# JLink-OB.net
KiCad netlist of a schematic drawn in EAGLE
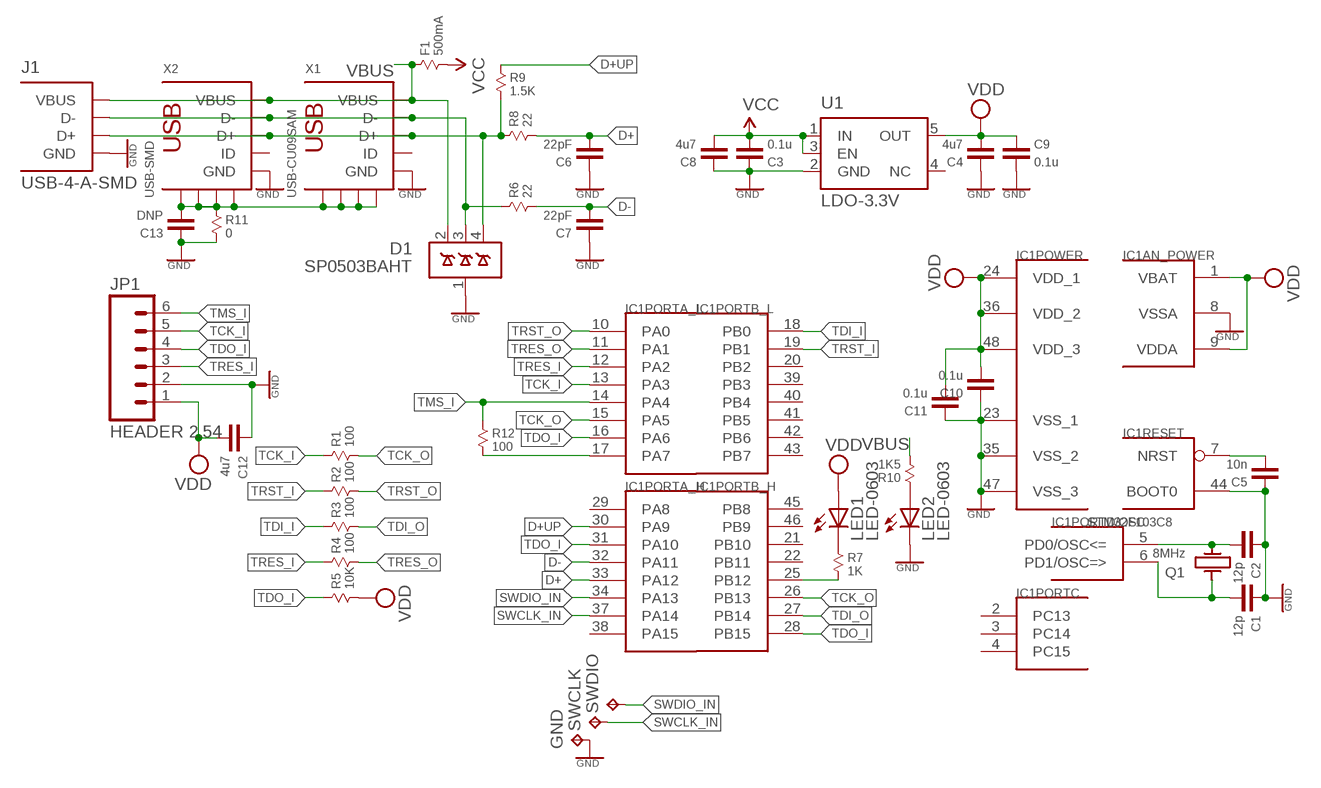
[diagram p0: schematic, sheet 1]

(export (version "E")
  (design (tool "Eeschema 10.0.6"))
  (components
    (comp (ref "C1")
      (value "12p")
      (footprint "eagle-import:0603")
      (libsource (lib "eagle-import") (part "CAP-0603"))
    )
    (comp (ref "C2")
      (value "12p")
      (footprint "eagle-import:0603")
      (libsource (lib "eagle-import") (part "CAP-0603"))
    )
    (comp (ref "C3")
      (value "0.1u")
      (footprint "eagle-import:0603")
      (libsource (lib "eagle-import") (part "CAP-0603"))
    )
    (comp (ref "C4")
      (value "4u7")
      (footprint "eagle-import:0603")
      (libsource (lib "eagle-import") (part "CAP-0603"))
    )
    (comp (ref "C5")
      (value "10n")
      (footprint "eagle-import:0603")
      (libsource (lib "eagle-import") (part "CAP-0603"))
    )
    (comp (ref "C6")
      (value "22pF")
      (footprint "eagle-import:0603")
      (libsource (lib "eagle-import") (part "CAP-0603"))
    )
    (comp (ref "C7")
      (value "22pF")
      (footprint "eagle-import:0603")
      (libsource (lib "eagle-import") (part "CAP-0603"))
    )
    (comp (ref "C8")
      (value "4u7")
      (footprint "eagle-import:0603")
      (libsource (lib "eagle-import") (part "CAP-0603"))
    )
    (comp (ref "C9")
      (value "0.1u")
      (footprint "eagle-import:0603")
      (libsource (lib "eagle-import") (part "CAP-0603"))
    )
    (comp (ref "C10")
      (value "0.1u")
      (footprint "eagle-import:0603")
      (libsource (lib "eagle-import") (part "CAP-0603"))
    )
    (comp (ref "C11")
      (value "0.1u")
      (footprint "eagle-import:0603")
      (libsource (lib "eagle-import") (part "CAP-0603"))
    )
    (comp (ref "C12")
      (value "4u7")
      (footprint "eagle-import:0603")
      (libsource (lib "eagle-import") (part "CAP-0603"))
    )
    (comp (ref "C13")
      (value "DNP")
      (footprint "eagle-import:0603")
      (libsource (lib "eagle-import") (part "CAP-0603"))
    )
    (comp (ref "D1")
      (value "SP0503BAHT")
      (footprint "eagle-import:SOT143")
      (libsource (lib "eagle-import") (part "SP0503BAHT"))
    )
    (comp (ref "F1")
      (value "500mA")
      (footprint "eagle-import:0805")
      (libsource (lib "eagle-import") (part "RESISTOR-0805"))
    )
    (comp (ref "GND")
      (value "TPTP12R")
      (footprint "eagle-import:TP12R")
      (libsource (lib "eagle-import") (part "TPTP12R"))
    )
    (comp (ref "IC1")
      (value "STM32F103C8")
      (footprint "eagle-import:TQFP48")
      (libsource (lib "eagle-import") (part "STM32F10XCXT6"))
    )
    (comp (ref "J1")
      (value "USB-4-A-SMD")
      (footprint "eagle-import:USB-A-SMD")
      (libsource (lib "eagle-import") (part "USB-4-A-SMD"))
    )
    (comp (ref "JP1")
      (value "HEADER 2.54")
      (footprint "eagle-import:1X06")
      (libsource (lib "eagle-import") (part "M06SIP"))
    )
    (comp (ref "LED1")
      (value "LED-0603")
      (footprint "eagle-import:CHIPLED_0603")
      (libsource (lib "eagle-import") (part "LEDCHIPLED_0603"))
    )
    (comp (ref "LED2")
      (value "LED-0603")
      (footprint "eagle-import:CHIPLED_0603")
      (libsource (lib "eagle-import") (part "LEDCHIPLED_0603"))
    )
    (comp (ref "Q1")
      (value "8MHz")
      (footprint "eagle-import:KX-9A")
      (libsource (lib "eagle-import") (part "CRYSTAL-KX-9A"))
    )
    (comp (ref "R1")
      (value "100")
      (footprint "eagle-import:0603")
      (libsource (lib "eagle-import") (part "RESISTOR-0603"))
    )
    (comp (ref "R2")
      (value "100")
      (footprint "eagle-import:0603")
      (libsource (lib "eagle-import") (part "RESISTOR-0603"))
    )
    (comp (ref "R3")
      (value "100")
      (footprint "eagle-import:0603")
      (libsource (lib "eagle-import") (part "RESISTOR-0603"))
    )
    (comp (ref "R4")
      (value "100")
      (footprint "eagle-import:0603")
      (libsource (lib "eagle-import") (part "RESISTOR-0603"))
    )
    (comp (ref "R5")
      (value "10K")
      (footprint "eagle-import:0603")
      (libsource (lib "eagle-import") (part "RESISTOR-0603"))
    )
    (comp (ref "R6")
      (value "22")
      (footprint "eagle-import:0603")
      (libsource (lib "eagle-import") (part "RESISTOR-0603"))
    )
    (comp (ref "R7")
      (value "1K")
      (footprint "eagle-import:0603")
      (libsource (lib "eagle-import") (part "RESISTOR-0603"))
    )
    (comp (ref "R8")
      (value "22")
      (footprint "eagle-import:0603")
      (libsource (lib "eagle-import") (part "RESISTOR-0603"))
    )
    (comp (ref "R9")
      (value "1.5K")
      (footprint "eagle-import:0603")
      (libsource (lib "eagle-import") (part "RESISTOR-0603"))
    )
    (comp (ref "R10")
      (value "1K5")
      (footprint "eagle-import:0603")
      (libsource (lib "eagle-import") (part "RESISTOR-0603"))
    )
    (comp (ref "R11")
      (value "0")
      (footprint "eagle-import:0603")
      (libsource (lib "eagle-import") (part "RESISTOR-0603"))
    )
    (comp (ref "R12")
      (value "100")
      (footprint "eagle-import:0603")
      (libsource (lib "eagle-import") (part "RESISTOR-0603"))
    )
    (comp (ref "SWCLK")
      (value "TPTP12R")
      (footprint "eagle-import:TP12R")
      (libsource (lib "eagle-import") (part "TPTP12R"))
    )
    (comp (ref "SWDIO")
      (value "TPTP12R")
      (footprint "eagle-import:TP12R")
      (libsource (lib "eagle-import") (part "TPTP12R"))
    )
    (comp (ref "U1")
      (value "LDO-3.3V")
      (footprint "eagle-import:SOT23-5")
      (libsource (lib "eagle-import") (part "TPS73033-DC"))
    )
    (comp (ref "X1")
      (value "USB-CU09SAM")
      (footprint "eagle-import:CU09SAM")
      (libsource (lib "eagle-import") (part "USB-CU09SAM"))
    )
    (comp (ref "X2")
      (value "USB-SMD")
      (footprint "eagle-import:USB-MINIB")
      (libsource (lib "eagle-import") (part "USB-SMD"))
    )
  )
  (nets
    (net (code "1") (name "/VBUS") (class "Default")
      (node (ref "D1") (pin "2") (pinfunction "D1_2") (pintype "passive"))
      (node (ref "F1") (pin "1") (pinfunction "1_1") (pintype "passive"))
      (node (ref "J1") (pin "VUSB") (pinfunction "VBUS_VUSB") (pintype "passive"))
      (node (ref "R10") (pin "2") (pinfunction "2_2") (pintype "passive"))
      (node (ref "X1") (pin "1") (pinfunction "VBUS_1") (pintype "passive"))
      (node (ref "X2") (pin "VBUS") (pinfunction "VBUS_VBUS") (pintype "passive"))
    )
    (net (code "2") (name "D+") (class "Default")
      (node (ref "C6") (pin "1") (pinfunction "1_1") (pintype "passive"))
      (node (ref "IC1") (pin "33") (pinfunction "PA12_33") (pintype "bidirectional"))
      (node (ref "R8") (pin "2") (pinfunction "2_2") (pintype "passive"))
    )
    (net (code "3") (name "D+UP") (class "Default")
      (node (ref "IC1") (pin "30") (pinfunction "PA9_30") (pintype "bidirectional"))
      (node (ref "R9") (pin "1") (pinfunction "1_1") (pintype "passive"))
    )
    (net (code "4") (name "D-") (class "Default")
      (node (ref "C7") (pin "1") (pinfunction "1_1") (pintype "passive"))
      (node (ref "IC1") (pin "32") (pinfunction "PA11_32") (pintype "bidirectional"))
      (node (ref "R6") (pin "2") (pinfunction "2_2") (pintype "passive"))
    )
    (net (code "5") (name "GND") (class "Default")
      (node (ref "C1") (pin "2") (pinfunction "2_2") (pintype "passive"))
      (node (ref "C10") (pin "2") (pinfunction "2_2") (pintype "passive"))
      (node (ref "C11") (pin "2") (pinfunction "2_2") (pintype "passive"))
      (node (ref "C12") (pin "2") (pinfunction "2_2") (pintype "passive"))
      (node (ref "C13") (pin "2") (pinfunction "2_2") (pintype "passive"))
      (node (ref "C2") (pin "2") (pinfunction "2_2") (pintype "passive"))
      (node (ref "C3") (pin "2") (pinfunction "2_2") (pintype "passive"))
      (node (ref "C4") (pin "2") (pinfunction "2_2") (pintype "passive"))
      (node (ref "C5") (pin "2") (pinfunction "2_2") (pintype "passive"))
      (node (ref "C6") (pin "2") (pinfunction "2_2") (pintype "passive"))
      (node (ref "C7") (pin "2") (pinfunction "2_2") (pintype "passive"))
      (node (ref "C8") (pin "2") (pinfunction "2_2") (pintype "passive"))
      (node (ref "C9") (pin "1") (pinfunction "1_1") (pintype "passive"))
      (node (ref "D1") (pin "1") (pinfunction "GND_1") (pintype "power_in"))
      (node (ref "GND") (pin "TP") (pinfunction "TP_TP") (pintype "input"))
      (node (ref "IC1") (pin "23") (pinfunction "VSS_1_23") (pintype "power_in"))
      (node (ref "IC1") (pin "35") (pinfunction "VSS_2_35") (pintype "power_in"))
      (node (ref "IC1") (pin "44") (pinfunction "BOOT0_44") (pintype "input"))
      (node (ref "IC1") (pin "47") (pinfunction "VSS_3_47") (pintype "power_in"))
      (node (ref "IC1") (pin "8") (pinfunction "VSSA_8") (pintype "power_in"))
      (node (ref "J1") (pin "GND") (pinfunction "GND_GND") (pintype "power_in"))
      (node (ref "JP1") (pin "2") (pinfunction "2_2") (pintype "passive"))
      (node (ref "LED2") (pin "C") (pinfunction "C_C") (pintype "passive"))
      (node (ref "R11") (pin "2") (pinfunction "2_2") (pintype "passive"))
      (node (ref "U1") (pin "2") (pinfunction "GND_2") (pintype "power_in"))
      (node (ref "X1") (pin "5") (pinfunction "GND_5") (pintype "power_in"))
      (node (ref "X2") (pin "GND") (pinfunction "GND_GND") (pintype "power_in"))
    )
    (net (code "6") (name "Net-(C13-Pad1)") (class "Default")
      (node (ref "C13") (pin "1") (pinfunction "1_1") (pintype "passive"))
      (node (ref "R11") (pin "1") (pinfunction "1_1") (pintype "passive"))
      (node (ref "X1") (pin "GND@1") (pinfunction "GND_GND@1") (pintype "power_in"))
      (node (ref "X1") (pin "GND@2") (pinfunction "GND_GND@2") (pintype "power_in"))
      (node (ref "X1") (pin "GND@3") (pinfunction "GND_GND@3") (pintype "power_in"))
      (node (ref "X1") (pin "GND@4") (pinfunction "GND_GND@4") (pintype "power_in"))
      (node (ref "X2") (pin "GND@1") (pinfunction "GND_GND@1") (pintype "power_in"))
      (node (ref "X2") (pin "GND@2") (pinfunction "GND_GND@2") (pintype "power_in"))
      (node (ref "X2") (pin "GND@3") (pinfunction "GND_GND@3") (pintype "power_in"))
      (node (ref "X2") (pin "GND@4") (pinfunction "GND_GND@4") (pintype "power_in"))
    )
    (net (code "7") (name "Net-(D1-D2)") (class "Default")
      (node (ref "D1") (pin "3") (pinfunction "D2_3") (pintype "passive"))
      (node (ref "J1") (pin "D-") (pinfunction "D-_D-") (pintype "bidirectional"))
      (node (ref "R6") (pin "1") (pinfunction "1_1") (pintype "passive"))
      (node (ref "X1") (pin "2") (pinfunction "D-_2") (pintype "bidirectional"))
      (node (ref "X2") (pin "D-") (pinfunction "D-_D-") (pintype "bidirectional"))
    )
    (net (code "8") (name "Net-(D1-D3)") (class "Default")
      (node (ref "D1") (pin "4") (pinfunction "D3_4") (pintype "passive"))
      (node (ref "J1") (pin "D+") (pinfunction "D+_D+") (pintype "bidirectional"))
      (node (ref "R8") (pin "1") (pinfunction "1_1") (pintype "passive"))
      (node (ref "R9") (pin "2") (pinfunction "2_2") (pintype "passive"))
      (node (ref "X1") (pin "3") (pinfunction "D+_3") (pintype "bidirectional"))
      (node (ref "X2") (pin "D+") (pinfunction "D+_D+") (pintype "bidirectional"))
    )
    (net (code "9") (name "Net-(IC1C-PA7)") (class "Default")
      (node (ref "IC1") (pin "17") (pinfunction "PA7_17") (pintype "bidirectional"))
      (node (ref "R12") (pin "2") (pinfunction "2_2") (pintype "passive"))
    )
    (net (code "10") (name "Net-(IC1D-PB12)") (class "Default")
      (node (ref "IC1") (pin "25") (pinfunction "PB12_25") (pintype "bidirectional"))
      (node (ref "R7") (pin "2") (pinfunction "2_2") (pintype "passive"))
    )
    (net (code "11") (name "Net-(IC1G-PD0{slash}OSC<=)") (class "Default")
      (node (ref "C2") (pin "1") (pinfunction "1_1") (pintype "passive"))
      (node (ref "IC1") (pin "5") (pinfunction "PD0/OSC<=_5") (pintype "bidirectional"))
      (node (ref "Q1") (pin "3") (pinfunction "2_3") (pintype "passive"))
    )
    (net (code "12") (name "Net-(IC1G-PD1{slash}OSC=>)") (class "Default")
      (node (ref "C1") (pin "1") (pinfunction "1_1") (pintype "passive"))
      (node (ref "IC1") (pin "6") (pinfunction "PD1/OSC=>_6") (pintype "bidirectional"))
      (node (ref "Q1") (pin "1") (pinfunction "1_1") (pintype "passive"))
    )
    (net (code "13") (name "Net-(IC1I-NRST)") (class "Default")
      (node (ref "C5") (pin "1") (pinfunction "1_1") (pintype "passive"))
      (node (ref "IC1") (pin "7") (pinfunction "NRST_7") (pintype "input"))
    )
    (net (code "14") (name "Net-(LED1-PadC)") (class "Default")
      (node (ref "LED1") (pin "C") (pinfunction "C_C") (pintype "passive"))
      (node (ref "R7") (pin "1") (pinfunction "1_1") (pintype "passive"))
    )
    (net (code "15") (name "Net-(LED2-PadA)") (class "Default")
      (node (ref "LED2") (pin "A") (pinfunction "A_A") (pintype "passive"))
      (node (ref "R10") (pin "1") (pinfunction "1_1") (pintype "passive"))
    )
    (net (code "16") (name "SWCLK_IN") (class "Default")
      (node (ref "IC1") (pin "37") (pinfunction "PA14_37") (pintype "bidirectional"))
      (node (ref "SWCLK") (pin "TP") (pinfunction "TP_TP") (pintype "input"))
    )
    (net (code "17") (name "SWDIO_IN") (class "Default")
      (node (ref "IC1") (pin "34") (pinfunction "PA13_34") (pintype "bidirectional"))
      (node (ref "SWDIO") (pin "TP") (pinfunction "TP_TP") (pintype "input"))
    )
    (net (code "18") (name "TCK_I") (class "Default")
      (node (ref "IC1") (pin "13") (pinfunction "PA3_13") (pintype "bidirectional"))
      (node (ref "JP1") (pin "5") (pinfunction "5_5") (pintype "passive"))
      (node (ref "R1") (pin "1") (pinfunction "1_1") (pintype "passive"))
    )
    (net (code "19") (name "TCK_O") (class "Default")
      (node (ref "IC1") (pin "15") (pinfunction "PA5_15") (pintype "bidirectional"))
      (node (ref "IC1") (pin "26") (pinfunction "PB13_26") (pintype "bidirectional"))
      (node (ref "R1") (pin "2") (pinfunction "2_2") (pintype "passive"))
    )
    (net (code "20") (name "TDI_I") (class "Default")
      (node (ref "IC1") (pin "18") (pinfunction "PB0_18") (pintype "bidirectional"))
      (node (ref "R3") (pin "1") (pinfunction "1_1") (pintype "passive"))
    )
    (net (code "21") (name "TDI_O") (class "Default")
      (node (ref "IC1") (pin "27") (pinfunction "PB14_27") (pintype "bidirectional"))
      (node (ref "R3") (pin "2") (pinfunction "2_2") (pintype "passive"))
    )
    (net (code "22") (name "TDO_I") (class "Default")
      (node (ref "IC1") (pin "16") (pinfunction "PA6_16") (pintype "bidirectional"))
      (node (ref "IC1") (pin "28") (pinfunction "PB15_28") (pintype "bidirectional"))
      (node (ref "IC1") (pin "31") (pinfunction "PA10_31") (pintype "bidirectional"))
      (node (ref "JP1") (pin "4") (pinfunction "4_4") (pintype "passive"))
      (node (ref "R5") (pin "1") (pinfunction "1_1") (pintype "passive"))
    )
    (net (code "23") (name "TMS_I") (class "Default")
      (node (ref "IC1") (pin "14") (pinfunction "PA4_14") (pintype "bidirectional"))
      (node (ref "JP1") (pin "6") (pinfunction "6_6") (pintype "passive"))
      (node (ref "R12") (pin "1") (pinfunction "1_1") (pintype "passive"))
    )
    (net (code "24") (name "TRES_I") (class "Default")
      (node (ref "IC1") (pin "12") (pinfunction "PA2_12") (pintype "bidirectional"))
      (node (ref "JP1") (pin "3") (pinfunction "3_3") (pintype "passive"))
      (node (ref "R4") (pin "1") (pinfunction "1_1") (pintype "passive"))
    )
    (net (code "25") (name "TRES_O") (class "Default")
      (node (ref "IC1") (pin "11") (pinfunction "PA1_11") (pintype "bidirectional"))
      (node (ref "R4") (pin "2") (pinfunction "2_2") (pintype "passive"))
    )
    (net (code "26") (name "TRST_I") (class "Default")
      (node (ref "IC1") (pin "19") (pinfunction "PB1_19") (pintype "bidirectional"))
      (node (ref "R2") (pin "1") (pinfunction "1_1") (pintype "passive"))
    )
    (net (code "27") (name "TRST_O") (class "Default")
      (node (ref "IC1") (pin "10") (pinfunction "PA0_10") (pintype "bidirectional"))
      (node (ref "R2") (pin "2") (pinfunction "2_2") (pintype "passive"))
    )
    (net (code "28") (name "VCC") (class "Default")
      (node (ref "C3") (pin "1") (pinfunction "1_1") (pintype "passive"))
      (node (ref "C8") (pin "1") (pinfunction "1_1") (pintype "passive"))
      (node (ref "F1") (pin "2") (pinfunction "2_2") (pintype "passive"))
      (node (ref "U1") (pin "1") (pinfunction "IN_1") (pintype "passive"))
      (node (ref "U1") (pin "3") (pinfunction "EN_3") (pintype "input"))
    )
    (net (code "29") (name "VDD") (class "Default")
      (node (ref "C10") (pin "1") (pinfunction "1_1") (pintype "passive"))
      (node (ref "C11") (pin "1") (pinfunction "1_1") (pintype "passive"))
      (node (ref "C12") (pin "1") (pinfunction "1_1") (pintype "passive"))
      (node (ref "C4") (pin "1") (pinfunction "1_1") (pintype "passive"))
      (node (ref "C9") (pin "2") (pinfunction "2_2") (pintype "passive"))
      (node (ref "IC1") (pin "1") (pinfunction "VBAT_1") (pintype "power_in"))
      (node (ref "IC1") (pin "24") (pinfunction "VDD_1_24") (pintype "power_in"))
      (node (ref "IC1") (pin "36") (pinfunction "VDD_2_36") (pintype "power_in"))
      (node (ref "IC1") (pin "48") (pinfunction "VDD_3_48") (pintype "power_in"))
      (node (ref "IC1") (pin "9") (pinfunction "VDDA_9") (pintype "power_in"))
      (node (ref "JP1") (pin "1") (pinfunction "1_1") (pintype "passive"))
      (node (ref "LED1") (pin "A") (pinfunction "A_A") (pintype "passive"))
      (node (ref "R5") (pin "2") (pinfunction "2_2") (pintype "passive"))
      (node (ref "U1") (pin "5") (pinfunction "OUT_5") (pintype "passive"))
    )
    (net (code "30") (name "unconnected-(IC1B-PA8-Pad29)") (class "Default")
      (node (ref "IC1") (pin "29") (pinfunction "PA8_29") (pintype "bidirectional"))
    )
    (net (code "31") (name "unconnected-(IC1B-PA15-Pad38)") (class "Default")
      (node (ref "IC1") (pin "38") (pinfunction "PA15_38") (pintype "bidirectional"))
    )
    (net (code "32") (name "unconnected-(IC1D-PB8-Pad45)") (class "Default")
      (node (ref "IC1") (pin "45") (pinfunction "PB8_45") (pintype "bidirectional"))
    )
    (net (code "33") (name "unconnected-(IC1D-PB9-Pad46)") (class "Default")
      (node (ref "IC1") (pin "46") (pinfunction "PB9_46") (pintype "bidirectional"))
    )
    (net (code "34") (name "unconnected-(IC1D-PB10-Pad21)") (class "Default")
      (node (ref "IC1") (pin "21") (pinfunction "PB10_21") (pintype "bidirectional"))
    )
    (net (code "35") (name "unconnected-(IC1D-PB11-Pad22)") (class "Default")
      (node (ref "IC1") (pin "22") (pinfunction "PB11_22") (pintype "bidirectional"))
    )
    (net (code "36") (name "unconnected-(IC1E-PB2-Pad20)") (class "Default")
      (node (ref "IC1") (pin "20") (pinfunction "PB2_20") (pintype "bidirectional"))
    )
    (net (code "37") (name "unconnected-(IC1E-PB3-Pad39)") (class "Default")
      (node (ref "IC1") (pin "39") (pinfunction "PB3_39") (pintype "bidirectional"))
    )
    (net (code "38") (name "unconnected-(IC1E-PB4-Pad40)") (class "Default")
      (node (ref "IC1") (pin "40") (pinfunction "PB4_40") (pintype "bidirectional"))
    )
    (net (code "39") (name "unconnected-(IC1E-PB5-Pad41)") (class "Default")
      (node (ref "IC1") (pin "41") (pinfunction "PB5_41") (pintype "bidirectional"))
    )
    (net (code "40") (name "unconnected-(IC1E-PB6-Pad42)") (class "Default")
      (node (ref "IC1") (pin "42") (pinfunction "PB6_42") (pintype "bidirectional"))
    )
    (net (code "41") (name "unconnected-(IC1E-PB7-Pad43)") (class "Default")
      (node (ref "IC1") (pin "43") (pinfunction "PB7_43") (pintype "bidirectional"))
    )
    (net (code "42") (name "unconnected-(IC1F-PC13-Pad2)") (class "Default")
      (node (ref "IC1") (pin "2") (pinfunction "PC13_2") (pintype "bidirectional"))
    )
    (net (code "43") (name "unconnected-(IC1F-PC14-Pad3)") (class "Default")
      (node (ref "IC1") (pin "3") (pinfunction "PC14_3") (pintype "bidirectional"))
    )
    (net (code "44") (name "unconnected-(IC1F-PC15-Pad4)") (class "Default")
      (node (ref "IC1") (pin "4") (pinfunction "PC15_4") (pintype "bidirectional"))
    )
    (net (code "45") (name "unconnected-(U1-NC-Pad4)") (class "Default")
      (node (ref "U1") (pin "4") (pinfunction "NC_4") (pintype "no_connect"))
    )
    (net (code "46") (name "unconnected-(X1-ID-Pad4)") (class "Default")
      (node (ref "X1") (pin "4") (pinfunction "ID_4") (pintype "bidirectional"))
    )
    (net (code "47") (name "unconnected-(X2-PadID)") (class "Default")
      (node (ref "X2") (pin "ID") (pinfunction "ID_ID") (pintype "bidirectional"))
    )
  )
)
